# Relays_Multiplexer.net
KiCad netlist of a schematic drawn in EAGLE
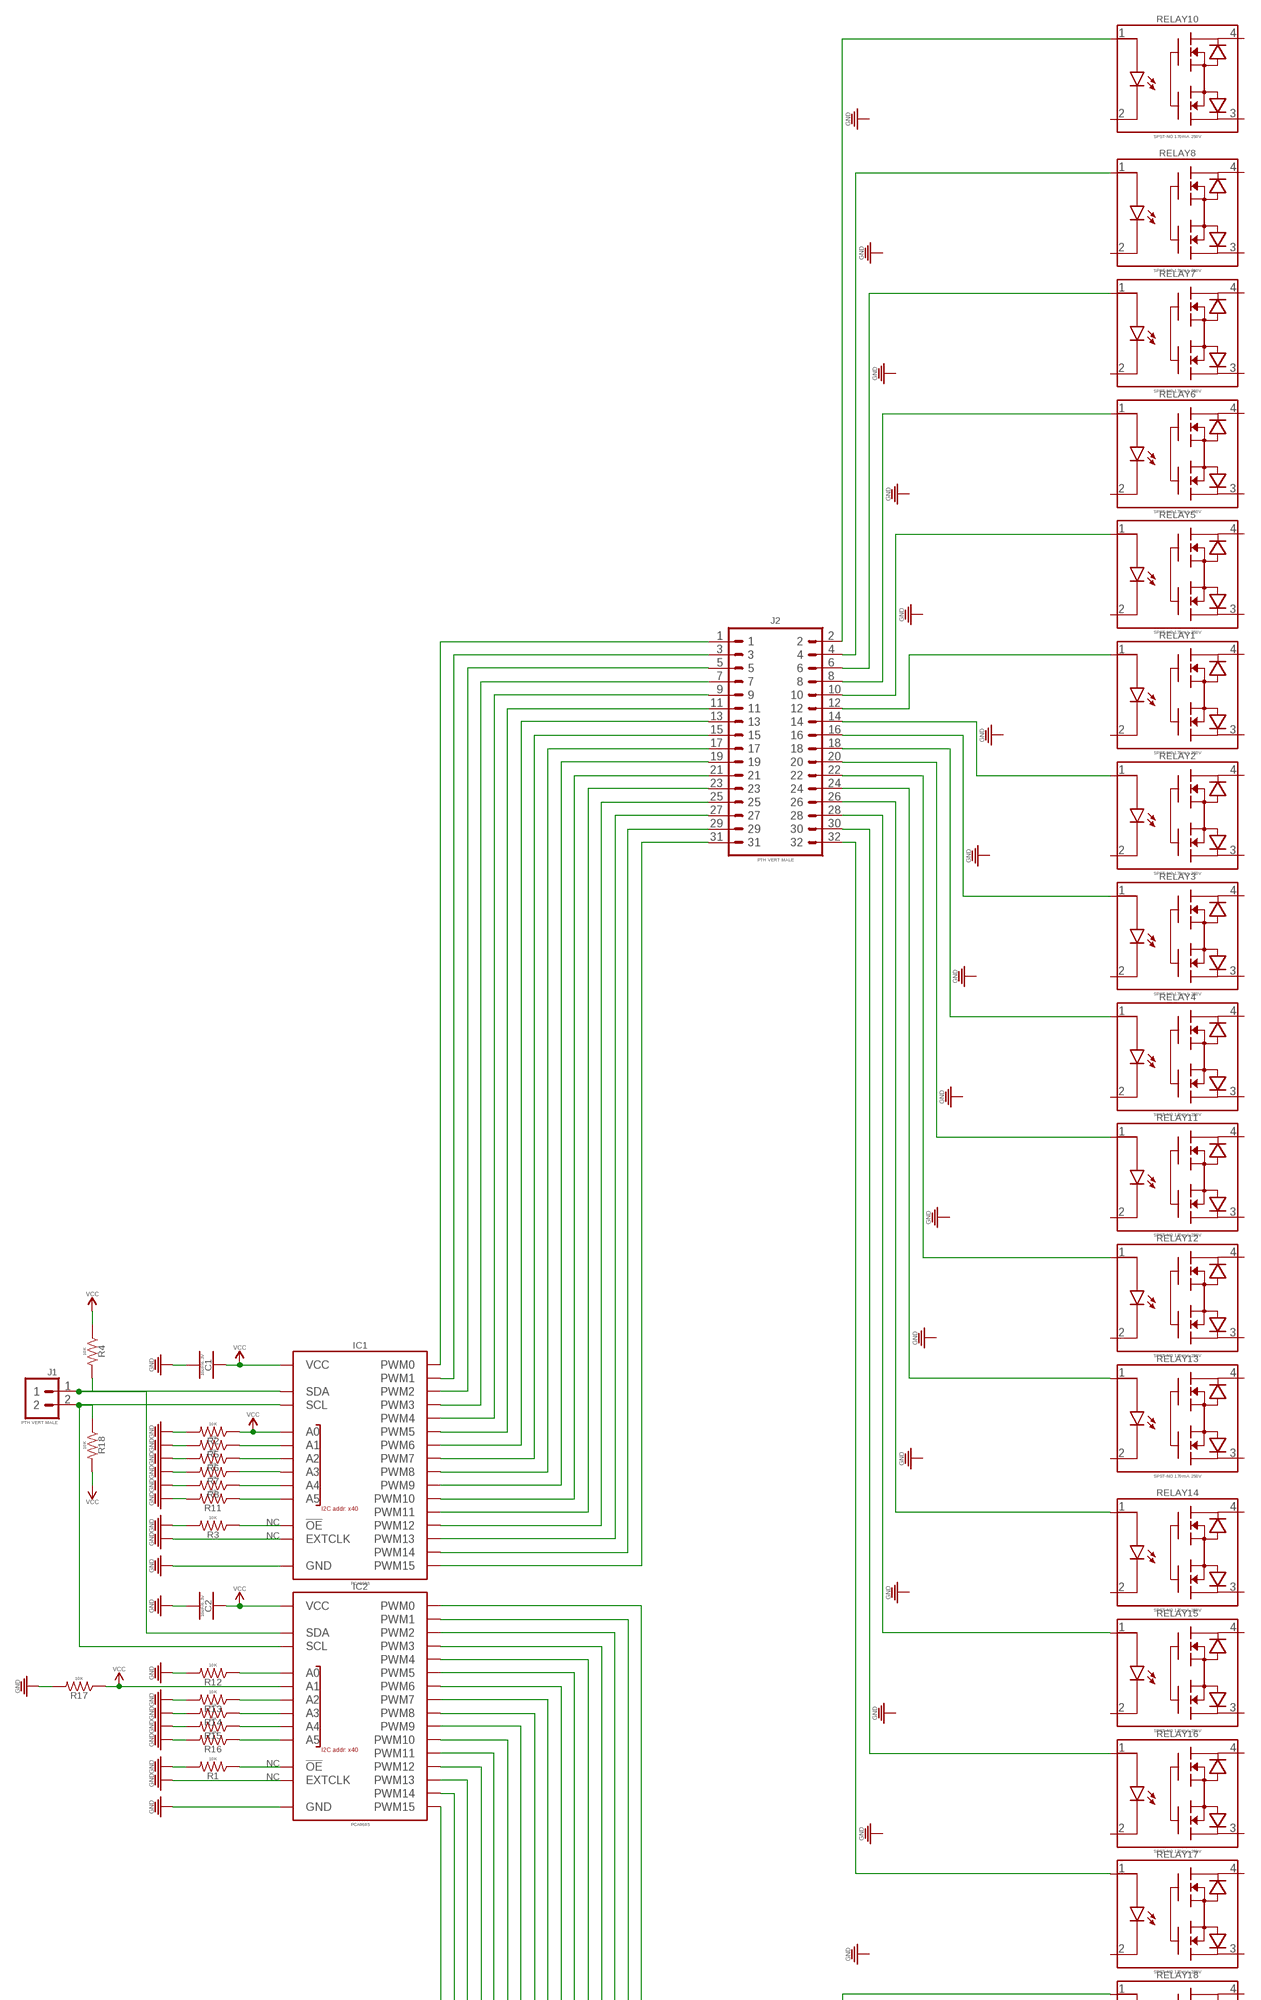
[diagram p0: schematic, sheet 1, part 1 of 2]
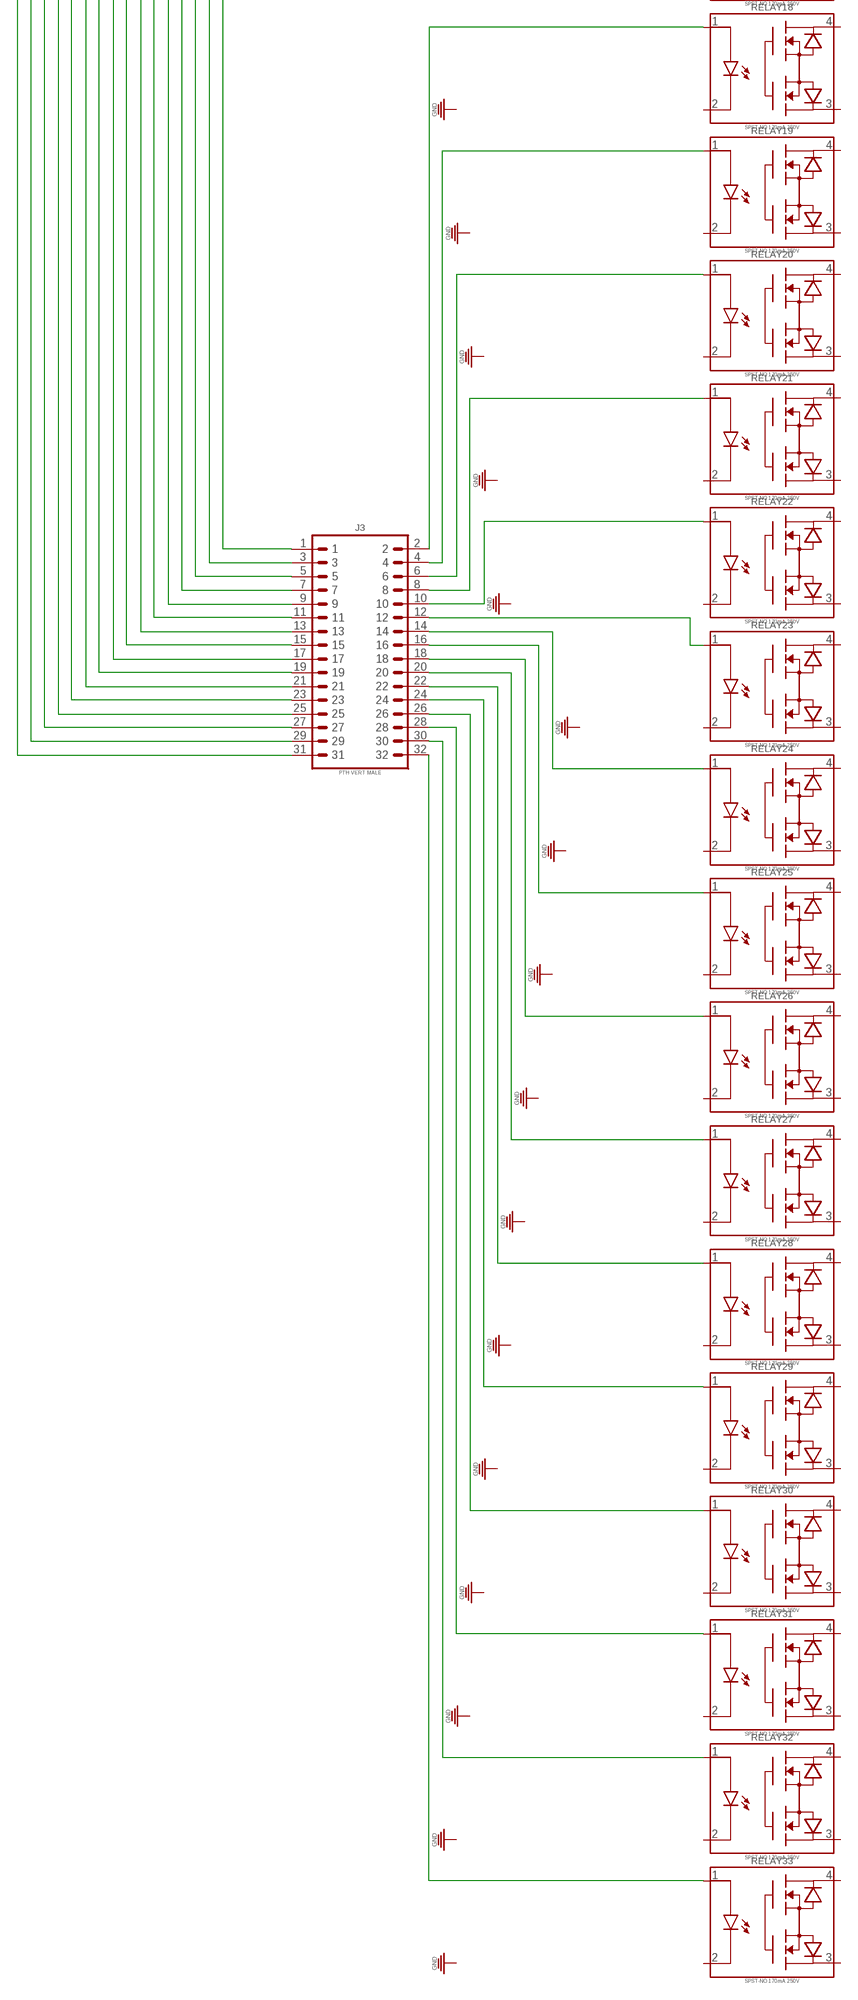
[diagram p1: schematic, sheet 1, part 2 of 2]

(export (version "E")
  (design (tool "Eeschema 10.0.6"))
  (components
    (comp (ref "C1")
      (value "10uF/6.3V")
      (footprint "eagle-import:CAPC1005X55_SMD-0402")
      (fields
        (field (name "MFR") "Murata Electronics North America")
        (field (name "MPN") "GRM155C80J106ME11D")
      )
      (libsource (lib "eagle-import") (part "10UF_CER_SMD-0402_6.3V-20%"))
    )
    (comp (ref "C2")
      (value "10uF/6.3V")
      (footprint "eagle-import:CAPC1005X55_SMD-0402")
      (fields
        (field (name "MFR") "Murata Electronics North America")
        (field (name "MPN") "GRM155C80J106ME11D")
      )
      (libsource (lib "eagle-import") (part "10UF_CER_SMD-0402_6.3V-20%"))
    )
    (comp (ref "IC1")
      (value "PCA9685")
      (footprint "eagle-import:SOP65P650X110-28")
      (fields (field (name "MFR") "NXP USA Inc.") (field (name "MPN") "PCA9685PW,118"))
      (libsource (lib "eagle-import") (part "PCA9685_16-CH_12-BIT_PWM-DRIVER_TSSOP-28_PWM-DRIVER_16CH"))
    )
    (comp (ref "IC2")
      (value "PCA9685")
      (footprint "eagle-import:SOP65P650X110-28")
      (fields (field (name "MFR") "NXP USA Inc.") (field (name "MPN") "PCA9685PW,118"))
      (libsource (lib "eagle-import") (part "PCA9685_16-CH_12-BIT_PWM-DRIVER_TSSOP-28_PWM-DRIVER_16CH"))
    )
    (comp (ref "J1")
      (value "PTH VERT MALE")
      (footprint "eagle-import:HDRV2W64P254_1X2_508X254X838B")
      (fields (field (name "MFR") "Sullins Connector Solutions") (field (name "MPN") "PEC02SAAN"))
      (libsource (lib "eagle-import") (part "1X02_PTH_VERT_MALE_2.54MM"))
    )
    (comp (ref "J2")
      (value "PTH VERT MALE")
      (footprint "eagle-import:HDRV32W64P254_2X16_4064X508X838B")
      (fields (field (name "MFR") "Sullins Connector Solutions") (field (name "MPN") "PEC16DAAN"))
      (libsource (lib "eagle-import") (part "2X16_PTH_VERT_MALE_2.54MM"))
    )
    (comp (ref "J3")
      (value "PTH VERT MALE")
      (footprint "eagle-import:HDRV32W64P254_2X16_4064X508X838B")
      (fields (field (name "MFR") "Sullins Connector Solutions") (field (name "MPN") "PEC16DAAN"))
      (libsource (lib "eagle-import") (part "2X16_PTH_VERT_MALE_2.54MM"))
    )
    (comp (ref "R1")
      (value "10K")
      (footprint "eagle-import:RESC1005X35_SMD-0402")
      (fields (field (name "MFR") "Yageo") (field (name "MPN") "RC0402JR-0710KP"))
      (libsource (lib "eagle-import") (part "10KΩ_SMD-0402_1/16W-5%"))
    )
    (comp (ref "R2")
      (value "10K")
      (footprint "eagle-import:RESC1005X35_SMD-0402")
      (fields (field (name "MFR") "Yageo") (field (name "MPN") "RC0402JR-0710KP"))
      (libsource (lib "eagle-import") (part "10KΩ_SMD-0402_1/16W-5%"))
    )
    (comp (ref "R3")
      (value "10K")
      (footprint "eagle-import:RESC1005X35_SMD-0402")
      (fields (field (name "MFR") "Yageo") (field (name "MPN") "RC0402JR-0710KP"))
      (libsource (lib "eagle-import") (part "10KΩ_SMD-0402_1/16W-5%"))
    )
    (comp (ref "R4")
      (value "10K")
      (footprint "eagle-import:RESC1005X35_SMD-0402")
      (fields (field (name "MFR") "Yageo") (field (name "MPN") "RC0402JR-0710KP"))
      (libsource (lib "eagle-import") (part "10KΩ_SMD-0402_1/16W-5%"))
    )
    (comp (ref "R5")
      (value "10K")
      (footprint "eagle-import:RESC1005X35_SMD-0402")
      (fields (field (name "MFR") "Yageo") (field (name "MPN") "RC0402JR-0710KP"))
      (libsource (lib "eagle-import") (part "10KΩ_SMD-0402_1/16W-5%"))
    )
    (comp (ref "R6")
      (value "10K")
      (footprint "eagle-import:RESC1005X35_SMD-0402")
      (fields (field (name "MFR") "Yageo") (field (name "MPN") "RC0402JR-0710KP"))
      (libsource (lib "eagle-import") (part "10KΩ_SMD-0402_1/16W-5%"))
    )
    (comp (ref "R7")
      (value "10K")
      (footprint "eagle-import:RESC1005X35_SMD-0402")
      (fields (field (name "MFR") "Yageo") (field (name "MPN") "RC0402JR-0710KP"))
      (libsource (lib "eagle-import") (part "10KΩ_SMD-0402_1/16W-5%"))
    )
    (comp (ref "R8")
      (value "10K")
      (footprint "eagle-import:RESC1005X35_SMD-0402")
      (fields (field (name "MFR") "Yageo") (field (name "MPN") "RC0402JR-0710KP"))
      (libsource (lib "eagle-import") (part "10KΩ_SMD-0402_1/16W-5%"))
    )
    (comp (ref "R11")
      (value "10K")
      (footprint "eagle-import:RESC1005X35_SMD-0402")
      (fields (field (name "MFR") "Yageo") (field (name "MPN") "RC0402JR-0710KP"))
      (libsource (lib "eagle-import") (part "10KΩ_SMD-0402_1/16W-5%"))
    )
    (comp (ref "R12")
      (value "10K")
      (footprint "eagle-import:RESC1005X35_SMD-0402")
      (fields (field (name "MFR") "Yageo") (field (name "MPN") "RC0402JR-0710KP"))
      (libsource (lib "eagle-import") (part "10KΩ_SMD-0402_1/16W-5%"))
    )
    (comp (ref "R13")
      (value "10K")
      (footprint "eagle-import:RESC1005X35_SMD-0402")
      (fields (field (name "MFR") "Yageo") (field (name "MPN") "RC0402JR-0710KP"))
      (libsource (lib "eagle-import") (part "10KΩ_SMD-0402_1/16W-5%"))
    )
    (comp (ref "R14")
      (value "10K")
      (footprint "eagle-import:RESC1005X35_SMD-0402")
      (fields (field (name "MFR") "Yageo") (field (name "MPN") "RC0402JR-0710KP"))
      (libsource (lib "eagle-import") (part "10KΩ_SMD-0402_1/16W-5%"))
    )
    (comp (ref "R15")
      (value "10K")
      (footprint "eagle-import:RESC1005X35_SMD-0402")
      (fields (field (name "MFR") "Yageo") (field (name "MPN") "RC0402JR-0710KP"))
      (libsource (lib "eagle-import") (part "10KΩ_SMD-0402_1/16W-5%"))
    )
    (comp (ref "R16")
      (value "10K")
      (footprint "eagle-import:RESC1005X35_SMD-0402")
      (fields (field (name "MFR") "Yageo") (field (name "MPN") "RC0402JR-0710KP"))
      (libsource (lib "eagle-import") (part "10KΩ_SMD-0402_1/16W-5%"))
    )
    (comp (ref "R17")
      (value "10K")
      (footprint "eagle-import:RESC1005X35_SMD-0402")
      (fields (field (name "MFR") "Yageo") (field (name "MPN") "RC0402JR-0710KP"))
      (libsource (lib "eagle-import") (part "10KΩ_SMD-0402_1/16W-5%"))
    )
    (comp (ref "R18")
      (value "10K")
      (footprint "eagle-import:RESC1005X35_SMD-0402")
      (fields (field (name "MFR") "Yageo") (field (name "MPN") "RC0402JR-0710KP"))
      (libsource (lib "eagle-import") (part "10KΩ_SMD-0402_1/16W-5%"))
    )
    (comp (ref "RELAY1")
      (value "SPST-NO 170mA 250V")
      (footprint "eagle-import:SOP254P609X203-4")
      (fields (field (name "MFR") "IXYS Integrated Circuits Division") (field (name "MPN") "CPC1010N"))
      (libsource (lib "eagle-import") (part "RELAY_SOLID-STATE_SSR_170MA_250V_SPST-NO"))
    )
    (comp (ref "RELAY2")
      (value "SPST-NO 170mA 250V")
      (footprint "eagle-import:SOP254P609X203-4")
      (fields (field (name "MFR") "IXYS Integrated Circuits Division") (field (name "MPN") "CPC1010N"))
      (libsource (lib "eagle-import") (part "RELAY_SOLID-STATE_SSR_170MA_250V_SPST-NO"))
    )
    (comp (ref "RELAY3")
      (value "SPST-NO 170mA 250V")
      (footprint "eagle-import:SOP254P609X203-4")
      (fields (field (name "MFR") "IXYS Integrated Circuits Division") (field (name "MPN") "CPC1010N"))
      (libsource (lib "eagle-import") (part "RELAY_SOLID-STATE_SSR_170MA_250V_SPST-NO"))
    )
    (comp (ref "RELAY4")
      (value "SPST-NO 170mA 250V")
      (footprint "eagle-import:SOP254P609X203-4")
      (fields (field (name "MFR") "IXYS Integrated Circuits Division") (field (name "MPN") "CPC1010N"))
      (libsource (lib "eagle-import") (part "RELAY_SOLID-STATE_SSR_170MA_250V_SPST-NO"))
    )
    (comp (ref "RELAY5")
      (value "SPST-NO 170mA 250V")
      (footprint "eagle-import:SOP254P609X203-4")
      (fields (field (name "MFR") "IXYS Integrated Circuits Division") (field (name "MPN") "CPC1010N"))
      (libsource (lib "eagle-import") (part "RELAY_SOLID-STATE_SSR_170MA_250V_SPST-NO"))
    )
    (comp (ref "RELAY6")
      (value "SPST-NO 170mA 250V")
      (footprint "eagle-import:SOP254P609X203-4")
      (fields (field (name "MFR") "IXYS Integrated Circuits Division") (field (name "MPN") "CPC1010N"))
      (libsource (lib "eagle-import") (part "RELAY_SOLID-STATE_SSR_170MA_250V_SPST-NO"))
    )
    (comp (ref "RELAY7")
      (value "SPST-NO 170mA 250V")
      (footprint "eagle-import:SOP254P609X203-4")
      (fields (field (name "MFR") "IXYS Integrated Circuits Division") (field (name "MPN") "CPC1010N"))
      (libsource (lib "eagle-import") (part "RELAY_SOLID-STATE_SSR_170MA_250V_SPST-NO"))
    )
    (comp (ref "RELAY8")
      (value "SPST-NO 170mA 250V")
      (footprint "eagle-import:SOP254P609X203-4")
      (fields (field (name "MFR") "IXYS Integrated Circuits Division") (field (name "MPN") "CPC1010N"))
      (libsource (lib "eagle-import") (part "RELAY_SOLID-STATE_SSR_170MA_250V_SPST-NO"))
    )
    (comp (ref "RELAY10")
      (value "SPST-NO 170mA 250V")
      (footprint "eagle-import:SOP254P609X203-4")
      (fields (field (name "MFR") "IXYS Integrated Circuits Division") (field (name "MPN") "CPC1010N"))
      (libsource (lib "eagle-import") (part "RELAY_SOLID-STATE_SSR_170MA_250V_SPST-NO"))
    )
    (comp (ref "RELAY11")
      (value "SPST-NO 170mA 250V")
      (footprint "eagle-import:SOP254P609X203-4")
      (fields (field (name "MFR") "IXYS Integrated Circuits Division") (field (name "MPN") "CPC1010N"))
      (libsource (lib "eagle-import") (part "RELAY_SOLID-STATE_SSR_170MA_250V_SPST-NO"))
    )
    (comp (ref "RELAY12")
      (value "SPST-NO 170mA 250V")
      (footprint "eagle-import:SOP254P609X203-4")
      (fields (field (name "MFR") "IXYS Integrated Circuits Division") (field (name "MPN") "CPC1010N"))
      (libsource (lib "eagle-import") (part "RELAY_SOLID-STATE_SSR_170MA_250V_SPST-NO"))
    )
    (comp (ref "RELAY13")
      (value "SPST-NO 170mA 250V")
      (footprint "eagle-import:SOP254P609X203-4")
      (fields (field (name "MFR") "IXYS Integrated Circuits Division") (field (name "MPN") "CPC1010N"))
      (libsource (lib "eagle-import") (part "RELAY_SOLID-STATE_SSR_170MA_250V_SPST-NO"))
    )
    (comp (ref "RELAY14")
      (value "SPST-NO 170mA 250V")
      (footprint "eagle-import:SOP254P609X203-4")
      (fields (field (name "MFR") "IXYS Integrated Circuits Division") (field (name "MPN") "CPC1010N"))
      (libsource (lib "eagle-import") (part "RELAY_SOLID-STATE_SSR_170MA_250V_SPST-NO"))
    )
    (comp (ref "RELAY15")
      (value "SPST-NO 170mA 250V")
      (footprint "eagle-import:SOP254P609X203-4")
      (fields (field (name "MFR") "IXYS Integrated Circuits Division") (field (name "MPN") "CPC1010N"))
      (libsource (lib "eagle-import") (part "RELAY_SOLID-STATE_SSR_170MA_250V_SPST-NO"))
    )
    (comp (ref "RELAY16")
      (value "SPST-NO 170mA 250V")
      (footprint "eagle-import:SOP254P609X203-4")
      (fields (field (name "MFR") "IXYS Integrated Circuits Division") (field (name "MPN") "CPC1010N"))
      (libsource (lib "eagle-import") (part "RELAY_SOLID-STATE_SSR_170MA_250V_SPST-NO"))
    )
    (comp (ref "RELAY17")
      (value "SPST-NO 170mA 250V")
      (footprint "eagle-import:SOP254P609X203-4")
      (fields (field (name "MFR") "IXYS Integrated Circuits Division") (field (name "MPN") "CPC1010N"))
      (libsource (lib "eagle-import") (part "RELAY_SOLID-STATE_SSR_170MA_250V_SPST-NO"))
    )
    (comp (ref "RELAY18")
      (value "SPST-NO 170mA 250V")
      (footprint "eagle-import:SOP254P609X203-4")
      (fields (field (name "MFR") "IXYS Integrated Circuits Division") (field (name "MPN") "CPC1010N"))
      (libsource (lib "eagle-import") (part "RELAY_SOLID-STATE_SSR_170MA_250V_SPST-NO"))
    )
    (comp (ref "RELAY19")
      (value "SPST-NO 170mA 250V")
      (footprint "eagle-import:SOP254P609X203-4")
      (fields (field (name "MFR") "IXYS Integrated Circuits Division") (field (name "MPN") "CPC1010N"))
      (libsource (lib "eagle-import") (part "RELAY_SOLID-STATE_SSR_170MA_250V_SPST-NO"))
    )
    (comp (ref "RELAY20")
      (value "SPST-NO 170mA 250V")
      (footprint "eagle-import:SOP254P609X203-4")
      (fields (field (name "MFR") "IXYS Integrated Circuits Division") (field (name "MPN") "CPC1010N"))
      (libsource (lib "eagle-import") (part "RELAY_SOLID-STATE_SSR_170MA_250V_SPST-NO"))
    )
    (comp (ref "RELAY21")
      (value "SPST-NO 170mA 250V")
      (footprint "eagle-import:SOP254P609X203-4")
      (fields (field (name "MFR") "IXYS Integrated Circuits Division") (field (name "MPN") "CPC1010N"))
      (libsource (lib "eagle-import") (part "RELAY_SOLID-STATE_SSR_170MA_250V_SPST-NO"))
    )
    (comp (ref "RELAY22")
      (value "SPST-NO 170mA 250V")
      (footprint "eagle-import:SOP254P609X203-4")
      (fields (field (name "MFR") "IXYS Integrated Circuits Division") (field (name "MPN") "CPC1010N"))
      (libsource (lib "eagle-import") (part "RELAY_SOLID-STATE_SSR_170MA_250V_SPST-NO"))
    )
    (comp (ref "RELAY23")
      (value "SPST-NO 170mA 250V")
      (footprint "eagle-import:SOP254P609X203-4")
      (fields (field (name "MFR") "IXYS Integrated Circuits Division") (field (name "MPN") "CPC1010N"))
      (libsource (lib "eagle-import") (part "RELAY_SOLID-STATE_SSR_170MA_250V_SPST-NO"))
    )
    (comp (ref "RELAY24")
      (value "SPST-NO 170mA 250V")
      (footprint "eagle-import:SOP254P609X203-4")
      (fields (field (name "MFR") "IXYS Integrated Circuits Division") (field (name "MPN") "CPC1010N"))
      (libsource (lib "eagle-import") (part "RELAY_SOLID-STATE_SSR_170MA_250V_SPST-NO"))
    )
    (comp (ref "RELAY25")
      (value "SPST-NO 170mA 250V")
      (footprint "eagle-import:SOP254P609X203-4")
      (fields (field (name "MFR") "IXYS Integrated Circuits Division") (field (name "MPN") "CPC1010N"))
      (libsource (lib "eagle-import") (part "RELAY_SOLID-STATE_SSR_170MA_250V_SPST-NO"))
    )
    (comp (ref "RELAY26")
      (value "SPST-NO 170mA 250V")
      (footprint "eagle-import:SOP254P609X203-4")
      (fields (field (name "MFR") "IXYS Integrated Circuits Division") (field (name "MPN") "CPC1010N"))
      (libsource (lib "eagle-import") (part "RELAY_SOLID-STATE_SSR_170MA_250V_SPST-NO"))
    )
    (comp (ref "RELAY27")
      (value "SPST-NO 170mA 250V")
      (footprint "eagle-import:SOP254P609X203-4")
      (fields (field (name "MFR") "IXYS Integrated Circuits Division") (field (name "MPN") "CPC1010N"))
      (libsource (lib "eagle-import") (part "RELAY_SOLID-STATE_SSR_170MA_250V_SPST-NO"))
    )
    (comp (ref "RELAY28")
      (value "SPST-NO 170mA 250V")
      (footprint "eagle-import:SOP254P609X203-4")
      (fields (field (name "MFR") "IXYS Integrated Circuits Division") (field (name "MPN") "CPC1010N"))
      (libsource (lib "eagle-import") (part "RELAY_SOLID-STATE_SSR_170MA_250V_SPST-NO"))
    )
    (comp (ref "RELAY29")
      (value "SPST-NO 170mA 250V")
      (footprint "eagle-import:SOP254P609X203-4")
      (fields (field (name "MFR") "IXYS Integrated Circuits Division") (field (name "MPN") "CPC1010N"))
      (libsource (lib "eagle-import") (part "RELAY_SOLID-STATE_SSR_170MA_250V_SPST-NO"))
    )
    (comp (ref "RELAY30")
      (value "SPST-NO 170mA 250V")
      (footprint "eagle-import:SOP254P609X203-4")
      (fields (field (name "MFR") "IXYS Integrated Circuits Division") (field (name "MPN") "CPC1010N"))
      (libsource (lib "eagle-import") (part "RELAY_SOLID-STATE_SSR_170MA_250V_SPST-NO"))
    )
    (comp (ref "RELAY31")
      (value "SPST-NO 170mA 250V")
      (footprint "eagle-import:SOP254P609X203-4")
      (fields (field (name "MFR") "IXYS Integrated Circuits Division") (field (name "MPN") "CPC1010N"))
      (libsource (lib "eagle-import") (part "RELAY_SOLID-STATE_SSR_170MA_250V_SPST-NO"))
    )
    (comp (ref "RELAY32")
      (value "SPST-NO 170mA 250V")
      (footprint "eagle-import:SOP254P609X203-4")
      (fields (field (name "MFR") "IXYS Integrated Circuits Division") (field (name "MPN") "CPC1010N"))
      (libsource (lib "eagle-import") (part "RELAY_SOLID-STATE_SSR_170MA_250V_SPST-NO"))
    )
    (comp (ref "RELAY33")
      (value "SPST-NO 170mA 250V")
      (footprint "eagle-import:SOP254P609X203-4")
      (fields (field (name "MFR") "IXYS Integrated Circuits Division") (field (name "MPN") "CPC1010N"))
      (libsource (lib "eagle-import") (part "RELAY_SOLID-STATE_SSR_170MA_250V_SPST-NO"))
    )
  )
  (nets
    (net (code "1") (name "GND") (class "Default")
      (node (ref "C1") (pin "2") (pinfunction "2_2") (pintype "passive"))
      (node (ref "C2") (pin "2") (pinfunction "2_2") (pintype "passive"))
      (node (ref "IC1") (pin "14") (pinfunction "GND_14") (pintype "power_in"))
      (node (ref "IC1") (pin "25") (pinfunction "EXTCLK_25") (pintype "power_in"))
      (node (ref "IC2") (pin "14") (pinfunction "GND_14") (pintype "power_in"))
      (node (ref "IC2") (pin "25") (pinfunction "EXTCLK_25") (pintype "power_in"))
      (node (ref "R1") (pin "2") (pinfunction "2_2") (pintype "passive"))
      (node (ref "R11") (pin "2") (pinfunction "2_2") (pintype "passive"))
      (node (ref "R12") (pin "2") (pinfunction "2_2") (pintype "passive"))
      (node (ref "R13") (pin "2") (pinfunction "2_2") (pintype "passive"))
      (node (ref "R14") (pin "2") (pinfunction "2_2") (pintype "passive"))
      (node (ref "R15") (pin "2") (pinfunction "2_2") (pintype "passive"))
      (node (ref "R16") (pin "2") (pinfunction "2_2") (pintype "passive"))
      (node (ref "R17") (pin "2") (pinfunction "2_2") (pintype "passive"))
      (node (ref "R2") (pin "2") (pinfunction "2_2") (pintype "passive"))
      (node (ref "R3") (pin "2") (pinfunction "2_2") (pintype "passive"))
      (node (ref "R5") (pin "2") (pinfunction "2_2") (pintype "passive"))
      (node (ref "R6") (pin "2") (pinfunction "2_2") (pintype "passive"))
      (node (ref "R7") (pin "2") (pinfunction "2_2") (pintype "passive"))
      (node (ref "R8") (pin "2") (pinfunction "2_2") (pintype "passive"))
    )
    (net (code "2") (name "Net-(IC1-A1)") (class "Default")
      (node (ref "IC1") (pin "2") (pinfunction "A1_2") (pintype "power_in"))
      (node (ref "R5") (pin "1") (pinfunction "1_1") (pintype "passive"))
    )
    (net (code "3") (name "Net-(IC1-A2)") (class "Default")
      (node (ref "IC1") (pin "3") (pinfunction "A2_3") (pintype "power_in"))
      (node (ref "R6") (pin "1") (pinfunction "1_1") (pintype "passive"))
    )
    (net (code "4") (name "Net-(IC1-A3)") (class "Default")
      (node (ref "IC1") (pin "4") (pinfunction "A3_4") (pintype "power_in"))
      (node (ref "R7") (pin "1") (pinfunction "1_1") (pintype "passive"))
    )
    (net (code "5") (name "Net-(IC1-A4)") (class "Default")
      (node (ref "IC1") (pin "5") (pinfunction "A4_5") (pintype "power_in"))
      (node (ref "R8") (pin "1") (pinfunction "1_1") (pintype "passive"))
    )
    (net (code "6") (name "Net-(IC1-A5)") (class "Default")
      (node (ref "IC1") (pin "24") (pinfunction "A5_24") (pintype "power_in"))
      (node (ref "R11") (pin "1") (pinfunction "1_1") (pintype "passive"))
    )
    (net (code "7") (name "Net-(IC1-PWM0)") (class "Default")
      (node (ref "IC1") (pin "6") (pinfunction "PWM0_6") (pintype "output"))
      (node (ref "J2") (pin "1") (pinfunction "1_1") (pintype "passive"))
    )
    (net (code "8") (name "Net-(IC1-PWM1)") (class "Default")
      (node (ref "IC1") (pin "7") (pinfunction "PWM1_7") (pintype "output"))
      (node (ref "J2") (pin "3") (pinfunction "3_3") (pintype "passive"))
    )
    (net (code "9") (name "Net-(IC1-PWM2)") (class "Default")
      (node (ref "IC1") (pin "8") (pinfunction "PWM2_8") (pintype "output"))
      (node (ref "J2") (pin "5") (pinfunction "5_5") (pintype "passive"))
    )
    (net (code "10") (name "Net-(IC1-PWM3)") (class "Default")
      (node (ref "IC1") (pin "9") (pinfunction "PWM3_9") (pintype "output"))
      (node (ref "J2") (pin "7") (pinfunction "7_7") (pintype "passive"))
    )
    (net (code "11") (name "Net-(IC1-PWM4)") (class "Default")
      (node (ref "IC1") (pin "10") (pinfunction "PWM4_10") (pintype "output"))
      (node (ref "J2") (pin "9") (pinfunction "9_9") (pintype "passive"))
    )
    (net (code "12") (name "Net-(IC1-PWM5)") (class "Default")
      (node (ref "IC1") (pin "11") (pinfunction "PWM5_11") (pintype "output"))
      (node (ref "J2") (pin "11") (pinfunction "11_11") (pintype "passive"))
    )
    (net (code "13") (name "Net-(IC1-PWM6)") (class "Default")
      (node (ref "IC1") (pin "12") (pinfunction "PWM6_12") (pintype "output"))
      (node (ref "J2") (pin "13") (pinfunction "13_13") (pintype "passive"))
    )
    (net (code "14") (name "Net-(IC1-PWM7)") (class "Default")
      (node (ref "IC1") (pin "13") (pinfunction "PWM7_13") (pintype "output"))
      (node (ref "J2") (pin "15") (pinfunction "15_15") (pintype "passive"))
    )
    (net (code "15") (name "Net-(IC1-PWM8)") (class "Default")
      (node (ref "IC1") (pin "15") (pinfunction "PWM8_15") (pintype "output"))
      (node (ref "J2") (pin "17") (pinfunction "17_17") (pintype "passive"))
    )
    (net (code "16") (name "Net-(IC1-PWM9)") (class "Default")
      (node (ref "IC1") (pin "16") (pinfunction "PWM9_16") (pintype "output"))
      (node (ref "J2") (pin "19") (pinfunction "19_19") (pintype "passive"))
    )
    (net (code "17") (name "Net-(IC1-PWM10)") (class "Default")
      (node (ref "IC1") (pin "17") (pinfunction "PWM10_17") (pintype "output"))
      (node (ref "J2") (pin "21") (pinfunction "21_21") (pintype "passive"))
    )
    (net (code "18") (name "Net-(IC1-PWM11)") (class "Default")
      (node (ref "IC1") (pin "18") (pinfunction "PWM11_18") (pintype "output"))
      (node (ref "J2") (pin "23") (pinfunction "23_23") (pintype "passive"))
    )
    (net (code "19") (name "Net-(IC1-PWM12)") (class "Default")
      (node (ref "IC1") (pin "19") (pinfunction "PWM12_19") (pintype "output"))
      (node (ref "J2") (pin "25") (pinfunction "25_25") (pintype "passive"))
    )
    (net (code "20") (name "Net-(IC1-PWM13)") (class "Default")
      (node (ref "IC1") (pin "20") (pinfunction "PWM13_20") (pintype "output"))
      (node (ref "J2") (pin "27") (pinfunction "27_27") (pintype "passive"))
    )
    (net (code "21") (name "Net-(IC1-PWM14)") (class "Default")
      (node (ref "IC1") (pin "21") (pinfunction "PWM14_21") (pintype "output"))
      (node (ref "J2") (pin "29") (pinfunction "29_29") (pintype "passive"))
    )
    (net (code "22") (name "Net-(IC1-PWM15)") (class "Default")
      (node (ref "IC1") (pin "22") (pinfunction "PWM15_22") (pintype "output"))
      (node (ref "J2") (pin "31") (pinfunction "31_31") (pintype "passive"))
    )
    (net (code "23") (name "Net-(IC1-SCL)") (class "Default")
      (node (ref "IC1") (pin "26") (pinfunction "SCL_26") (pintype "bidirectional"))
      (node (ref "IC2") (pin "26") (pinfunction "SCL_26") (pintype "bidirectional"))
      (node (ref "J1") (pin "2") (pinfunction "2_2") (pintype "passive"))
      (node (ref "R18") (pin "1") (pinfunction "1_1") (pintype "passive"))
    )
    (net (code "24") (name "Net-(IC1-SDA)") (class "Default")
      (node (ref "IC1") (pin "27") (pinfunction "SDA_27") (pintype "bidirectional"))
      (node (ref "IC2") (pin "27") (pinfunction "SDA_27") (pintype "bidirectional"))
      (node (ref "J1") (pin "1") (pinfunction "1_1") (pintype "passive"))
      (node (ref "R4") (pin "2") (pinfunction "2_2") (pintype "passive"))
    )
    (net (code "25") (name "Net-(IC1-~{OE})") (class "Default")
      (node (ref "IC1") (pin "23") (pinfunction "~{OE}_23") (pintype "power_in"))
      (node (ref "R3") (pin "1") (pinfunction "1_1") (pintype "passive"))
    )
    (net (code "26") (name "Net-(IC2-A0)") (class "Default")
      (node (ref "IC2") (pin "1") (pinfunction "A0_1") (pintype "power_in"))
      (node (ref "R12") (pin "1") (pinfunction "1_1") (pintype "passive"))
    )
    (net (code "27") (name "Net-(IC2-A2)") (class "Default")
      (node (ref "IC2") (pin "3") (pinfunction "A2_3") (pintype "power_in"))
      (node (ref "R13") (pin "1") (pinfunction "1_1") (pintype "passive"))
    )
    (net (code "28") (name "Net-(IC2-A3)") (class "Default")
      (node (ref "IC2") (pin "4") (pinfunction "A3_4") (pintype "power_in"))
      (node (ref "R14") (pin "1") (pinfunction "1_1") (pintype "passive"))
    )
    (net (code "29") (name "Net-(IC2-A4)") (class "Default")
      (node (ref "IC2") (pin "5") (pinfunction "A4_5") (pintype "power_in"))
      (node (ref "R15") (pin "1") (pinfunction "1_1") (pintype "passive"))
    )
    (net (code "30") (name "Net-(IC2-A5)") (class "Default")
      (node (ref "IC2") (pin "24") (pinfunction "A5_24") (pintype "power_in"))
      (node (ref "R16") (pin "1") (pinfunction "1_1") (pintype "passive"))
    )
    (net (code "31") (name "Net-(IC2-PWM0)") (class "Default")
      (node (ref "IC2") (pin "6") (pinfunction "PWM0_6") (pintype "output"))
      (node (ref "J3") (pin "1") (pinfunction "1_1") (pintype "passive"))
    )
    (net (code "32") (name "Net-(IC2-PWM1)") (class "Default")
      (node (ref "IC2") (pin "7") (pinfunction "PWM1_7") (pintype "output"))
      (node (ref "J3") (pin "3") (pinfunction "3_3") (pintype "passive"))
    )
    (net (code "33") (name "Net-(IC2-PWM2)") (class "Default")
      (node (ref "IC2") (pin "8") (pinfunction "PWM2_8") (pintype "output"))
      (node (ref "J3") (pin "5") (pinfunction "5_5") (pintype "passive"))
    )
    (net (code "34") (name "Net-(IC2-PWM3)") (class "Default")
      (node (ref "IC2") (pin "9") (pinfunction "PWM3_9") (pintype "output"))
      (node (ref "J3") (pin "7") (pinfunction "7_7") (pintype "passive"))
    )
    (net (code "35") (name "Net-(IC2-PWM4)") (class "Default")
      (node (ref "IC2") (pin "10") (pinfunction "PWM4_10") (pintype "output"))
      (node (ref "J3") (pin "9") (pinfunction "9_9") (pintype "passive"))
    )
    (net (code "36") (name "Net-(IC2-PWM5)") (class "Default")
      (node (ref "IC2") (pin "11") (pinfunction "PWM5_11") (pintype "output"))
      (node (ref "J3") (pin "11") (pinfunction "11_11") (pintype "passive"))
    )
    (net (code "37") (name "Net-(IC2-PWM6)") (class "Default")
      (node (ref "IC2") (pin "12") (pinfunction "PWM6_12") (pintype "output"))
      (node (ref "J3") (pin "13") (pinfunction "13_13") (pintype "passive"))
    )
    (net (code "38") (name "Net-(IC2-PWM7)") (class "Default")
      (node (ref "IC2") (pin "13") (pinfunction "PWM7_13") (pintype "output"))
      (node (ref "J3") (pin "15") (pinfunction "15_15") (pintype "passive"))
    )
    (net (code "39") (name "Net-(IC2-PWM8)") (class "Default")
      (node (ref "IC2") (pin "15") (pinfunction "PWM8_15") (pintype "output"))
      (node (ref "J3") (pin "17") (pinfunction "17_17") (pintype "passive"))
    )
    (net (code "40") (name "Net-(IC2-PWM9)") (class "Default")
      (node (ref "IC2") (pin "16") (pinfunction "PWM9_16") (pintype "output"))
      (node (ref "J3") (pin "19") (pinfunction "19_19") (pintype "passive"))
    )
    (net (code "41") (name "Net-(IC2-PWM10)") (class "Default")
      (node (ref "IC2") (pin "17") (pinfunction "PWM10_17") (pintype "output"))
      (node (ref "J3") (pin "21") (pinfunction "21_21") (pintype "passive"))
    )
    (net (code "42") (name "Net-(IC2-PWM11)") (class "Default")
      (node (ref "IC2") (pin "18") (pinfunction "PWM11_18") (pintype "output"))
      (node (ref "J3") (pin "23") (pinfunction "23_23") (pintype "passive"))
    )
    (net (code "43") (name "Net-(IC2-PWM12)") (class "Default")
      (node (ref "IC2") (pin "19") (pinfunction "PWM12_19") (pintype "output"))
      (node (ref "J3") (pin "25") (pinfunction "25_25") (pintype "passive"))
    )
    (net (code "44") (name "Net-(IC2-PWM13)") (class "Default")
      (node (ref "IC2") (pin "20") (pinfunction "PWM13_20") (pintype "output"))
      (node (ref "J3") (pin "27") (pinfunction "27_27") (pintype "passive"))
    )
    (net (code "45") (name "Net-(IC2-PWM14)") (class "Default")
      (node (ref "IC2") (pin "21") (pinfunction "PWM14_21") (pintype "output"))
      (node (ref "J3") (pin "29") (pinfunction "29_29") (pintype "passive"))
    )
    (net (code "46") (name "Net-(IC2-PWM15)") (class "Default")
      (node (ref "IC2") (pin "22") (pinfunction "PWM15_22") (pintype "output"))
      (node (ref "J3") (pin "31") (pinfunction "31_31") (pintype "passive"))
    )
    (net (code "47") (name "Net-(IC2-~{OE})") (class "Default")
      (node (ref "IC2") (pin "23") (pinfunction "~{OE}_23") (pintype "power_in"))
      (node (ref "R1") (pin "1") (pinfunction "1_1") (pintype "passive"))
    )
    (net (code "48") (name "Net-(J2-Pad2)") (class "Default")
      (node (ref "J2") (pin "2") (pinfunction "2_2") (pintype "passive"))
      (node (ref "RELAY10") (pin "1") (pinfunction "1_1") (pintype "bidirectional"))
    )
    (net (code "49") (name "Net-(J2-Pad4)") (class "Default")
      (node (ref "J2") (pin "4") (pinfunction "4_4") (pintype "passive"))
      (node (ref "RELAY8") (pin "1") (pinfunction "1_1") (pintype "bidirectional"))
    )
    (net (code "50") (name "Net-(J2-Pad6)") (class "Default")
      (node (ref "J2") (pin "6") (pinfunction "6_6") (pintype "passive"))
      (node (ref "RELAY7") (pin "1") (pinfunction "1_1") (pintype "bidirectional"))
    )
    (net (code "51") (name "Net-(J2-Pad8)") (class "Default")
      (node (ref "J2") (pin "8") (pinfunction "8_8") (pintype "passive"))
      (node (ref "RELAY6") (pin "1") (pinfunction "1_1") (pintype "bidirectional"))
    )
    (net (code "52") (name "Net-(J2-Pad10)") (class "Default")
      (node (ref "J2") (pin "10") (pinfunction "10_10") (pintype "passive"))
      (node (ref "RELAY5") (pin "1") (pinfunction "1_1") (pintype "bidirectional"))
    )
    (net (code "53") (name "Net-(J2-Pad12)") (class "Default")
      (node (ref "J2") (pin "12") (pinfunction "12_12") (pintype "passive"))
      (node (ref "RELAY1") (pin "1") (pinfunction "1_1") (pintype "bidirectional"))
    )
    (net (code "54") (name "Net-(J2-Pad14)") (class "Default")
      (node (ref "J2") (pin "14") (pinfunction "14_14") (pintype "passive"))
      (node (ref "RELAY2") (pin "1") (pinfunction "1_1") (pintype "bidirectional"))
    )
    (net (code "55") (name "Net-(J2-Pad16)") (class "Default")
      (node (ref "J2") (pin "16") (pinfunction "16_16") (pintype "passive"))
      (node (ref "RELAY3") (pin "1") (pinfunction "1_1") (pintype "bidirectional"))
    )
    (net (code "56") (name "Net-(J2-Pad18)") (class "Default")
      (node (ref "J2") (pin "18") (pinfunction "18_18") (pintype "passive"))
      (node (ref "RELAY4") (pin "1") (pinfunction "1_1") (pintype "bidirectional"))
    )
    (net (code "57") (name "Net-(J2-Pad20)") (class "Default")
      (node (ref "J2") (pin "20") (pinfunction "20_20") (pintype "passive"))
      (node (ref "RELAY11") (pin "1") (pinfunction "1_1") (pintype "bidirectional"))
    )
    (net (code "58") (name "Net-(J2-Pad22)") (class "Default")
      (node (ref "J2") (pin "22") (pinfunction "22_22") (pintype "passive"))
      (node (ref "RELAY12") (pin "1") (pinfunction "1_1") (pintype "bidirectional"))
    )
    (net (code "59") (name "Net-(J2-Pad24)") (class "Default")
      (node (ref "J2") (pin "24") (pinfunction "24_24") (pintype "passive"))
      (node (ref "RELAY13") (pin "1") (pinfunction "1_1") (pintype "bidirectional"))
    )
    (net (code "60") (name "Net-(J2-Pad26)") (class "Default")
      (node (ref "J2") (pin "26") (pinfunction "26_26") (pintype "passive"))
      (node (ref "RELAY14") (pin "1") (pinfunction "1_1") (pintype "bidirectional"))
    )
    (net (code "61") (name "Net-(J2-Pad28)") (class "Default")
      (node (ref "J2") (pin "28") (pinfunction "28_28") (pintype "passive"))
      (node (ref "RELAY15") (pin "1") (pinfunction "1_1") (pintype "bidirectional"))
    )
    (net (code "62") (name "Net-(J2-Pad30)") (class "Default")
      (node (ref "J2") (pin "30") (pinfunction "30_30") (pintype "passive"))
      (node (ref "RELAY16") (pin "1") (pinfunction "1_1") (pintype "bidirectional"))
    )
    (net (code "63") (name "Net-(J2-Pad32)") (class "Default")
      (node (ref "J2") (pin "32") (pinfunction "32_32") (pintype "passive"))
      (node (ref "RELAY17") (pin "1") (pinfunction "1_1") (pintype "bidirectional"))
    )
    (net (code "64") (name "Net-(J3-Pad2)") (class "Default")
      (node (ref "J3") (pin "2") (pinfunction "2_2") (pintype "passive"))
      (node (ref "RELAY18") (pin "1") (pinfunction "1_1") (pintype "bidirectional"))
    )
    (net (code "65") (name "Net-(J3-Pad4)") (class "Default")
      (node (ref "J3") (pin "4") (pinfunction "4_4") (pintype "passive"))
      (node (ref "RELAY19") (pin "1") (pinfunction "1_1") (pintype "bidirectional"))
    )
    (net (code "66") (name "Net-(J3-Pad6)") (class "Default")
      (node (ref "J3") (pin "6") (pinfunction "6_6") (pintype "passive"))
      (node (ref "RELAY20") (pin "1") (pinfunction "1_1") (pintype "bidirectional"))
    )
    (net (code "67") (name "Net-(J3-Pad8)") (class "Default")
      (node (ref "J3") (pin "8") (pinfunction "8_8") (pintype "passive"))
      (node (ref "RELAY21") (pin "1") (pinfunction "1_1") (pintype "bidirectional"))
    )
    (net (code "68") (name "Net-(J3-Pad10)") (class "Default")
      (node (ref "J3") (pin "10") (pinfunction "10_10") (pintype "passive"))
      (node (ref "RELAY22") (pin "1") (pinfunction "1_1") (pintype "bidirectional"))
    )
    (net (code "69") (name "Net-(J3-Pad12)") (class "Default")
      (node (ref "J3") (pin "12") (pinfunction "12_12") (pintype "passive"))
      (node (ref "RELAY23") (pin "1") (pinfunction "1_1") (pintype "bidirectional"))
    )
    (net (code "70") (name "Net-(J3-Pad14)") (class "Default")
      (node (ref "J3") (pin "14") (pinfunction "14_14") (pintype "passive"))
      (node (ref "RELAY24") (pin "1") (pinfunction "1_1") (pintype "bidirectional"))
    )
    (net (code "71") (name "Net-(J3-Pad16)") (class "Default")
      (node (ref "J3") (pin "16") (pinfunction "16_16") (pintype "passive"))
      (node (ref "RELAY25") (pin "1") (pinfunction "1_1") (pintype "bidirectional"))
    )
    (net (code "72") (name "Net-(J3-Pad18)") (class "Default")
      (node (ref "J3") (pin "18") (pinfunction "18_18") (pintype "passive"))
      (node (ref "RELAY26") (pin "1") (pinfunction "1_1") (pintype "bidirectional"))
    )
    (net (code "73") (name "Net-(J3-Pad20)") (class "Default")
      (node (ref "J3") (pin "20") (pinfunction "20_20") (pintype "passive"))
      (node (ref "RELAY27") (pin "1") (pinfunction "1_1") (pintype "bidirectional"))
    )
    (net (code "74") (name "Net-(J3-Pad22)") (class "Default")
      (node (ref "J3") (pin "22") (pinfunction "22_22") (pintype "passive"))
      (node (ref "RELAY28") (pin "1") (pinfunction "1_1") (pintype "bidirectional"))
    )
    (net (code "75") (name "Net-(J3-Pad24)") (class "Default")
      (node (ref "J3") (pin "24") (pinfunction "24_24") (pintype "passive"))
      (node (ref "RELAY29") (pin "1") (pinfunction "1_1") (pintype "bidirectional"))
    )
    (net (code "76") (name "Net-(J3-Pad26)") (class "Default")
      (node (ref "J3") (pin "26") (pinfunction "26_26") (pintype "passive"))
      (node (ref "RELAY30") (pin "1") (pinfunction "1_1") (pintype "bidirectional"))
    )
    (net (code "77") (name "Net-(J3-Pad28)") (class "Default")
      (node (ref "J3") (pin "28") (pinfunction "28_28") (pintype "passive"))
      (node (ref "RELAY31") (pin "1") (pinfunction "1_1") (pintype "bidirectional"))
    )
    (net (code "78") (name "Net-(J3-Pad30)") (class "Default")
      (node (ref "J3") (pin "30") (pinfunction "30_30") (pintype "passive"))
      (node (ref "RELAY32") (pin "1") (pinfunction "1_1") (pintype "bidirectional"))
    )
    (net (code "79") (name "Net-(J3-Pad32)") (class "Default")
      (node (ref "J3") (pin "32") (pinfunction "32_32") (pintype "passive"))
      (node (ref "RELAY33") (pin "1") (pinfunction "1_1") (pintype "bidirectional"))
    )
    (net (code "80") (name "VCC") (class "Default")
      (node (ref "C1") (pin "1") (pinfunction "1_1") (pintype "passive"))
      (node (ref "C2") (pin "1") (pinfunction "1_1") (pintype "passive"))
      (node (ref "IC1") (pin "1") (pinfunction "A0_1") (pintype "power_in"))
      (node (ref "IC1") (pin "28") (pinfunction "VCC_28") (pintype "power_in"))
      (node (ref "IC2") (pin "2") (pinfunction "A1_2") (pintype "power_in"))
      (node (ref "IC2") (pin "28") (pinfunction "VCC_28") (pintype "power_in"))
      (node (ref "R17") (pin "1") (pinfunction "1_1") (pintype "passive"))
      (node (ref "R18") (pin "2") (pinfunction "2_2") (pintype "passive"))
      (node (ref "R2") (pin "1") (pinfunction "1_1") (pintype "passive"))
      (node (ref "R4") (pin "1") (pinfunction "1_1") (pintype "passive"))
    )
    (net (code "81") (name "unconnected-(RELAY1-Pad2)") (class "Default")
      (node (ref "RELAY1") (pin "2") (pinfunction "2_2") (pintype "bidirectional"))
    )
    (net (code "82") (name "unconnected-(RELAY1-Pad3)") (class "Default")
      (node (ref "RELAY1") (pin "3") (pinfunction "3_3") (pintype "bidirectional"))
    )
    (net (code "83") (name "unconnected-(RELAY1-Pad4)") (class "Default")
      (node (ref "RELAY1") (pin "4") (pinfunction "4_4") (pintype "bidirectional"))
    )
    (net (code "84") (name "unconnected-(RELAY2-Pad2)") (class "Default")
      (node (ref "RELAY2") (pin "2") (pinfunction "2_2") (pintype "bidirectional"))
    )
    (net (code "85") (name "unconnected-(RELAY2-Pad3)") (class "Default")
      (node (ref "RELAY2") (pin "3") (pinfunction "3_3") (pintype "bidirectional"))
    )
    (net (code "86") (name "unconnected-(RELAY2-Pad4)") (class "Default")
      (node (ref "RELAY2") (pin "4") (pinfunction "4_4") (pintype "bidirectional"))
    )
    (net (code "87") (name "unconnected-(RELAY3-Pad2)") (class "Default")
      (node (ref "RELAY3") (pin "2") (pinfunction "2_2") (pintype "bidirectional"))
    )
    (net (code "88") (name "unconnected-(RELAY3-Pad3)") (class "Default")
      (node (ref "RELAY3") (pin "3") (pinfunction "3_3") (pintype "bidirectional"))
    )
    (net (code "89") (name "unconnected-(RELAY3-Pad4)") (class "Default")
      (node (ref "RELAY3") (pin "4") (pinfunction "4_4") (pintype "bidirectional"))
    )
    (net (code "90") (name "unconnected-(RELAY4-Pad2)") (class "Default")
      (node (ref "RELAY4") (pin "2") (pinfunction "2_2") (pintype "bidirectional"))
    )
    (net (code "91") (name "unconnected-(RELAY4-Pad3)") (class "Default")
      (node (ref "RELAY4") (pin "3") (pinfunction "3_3") (pintype "bidirectional"))
    )
    (net (code "92") (name "unconnected-(RELAY4-Pad4)") (class "Default")
      (node (ref "RELAY4") (pin "4") (pinfunction "4_4") (pintype "bidirectional"))
    )
    (net (code "93") (name "unconnected-(RELAY5-Pad2)") (class "Default")
      (node (ref "RELAY5") (pin "2") (pinfunction "2_2") (pintype "bidirectional"))
    )
    (net (code "94") (name "unconnected-(RELAY5-Pad3)") (class "Default")
      (node (ref "RELAY5") (pin "3") (pinfunction "3_3") (pintype "bidirectional"))
    )
    (net (code "95") (name "unconnected-(RELAY5-Pad4)") (class "Default")
      (node (ref "RELAY5") (pin "4") (pinfunction "4_4") (pintype "bidirectional"))
    )
    (net (code "96") (name "unconnected-(RELAY6-Pad2)") (class "Default")
      (node (ref "RELAY6") (pin "2") (pinfunction "2_2") (pintype "bidirectional"))
    )
    (net (code "97") (name "unconnected-(RELAY6-Pad3)") (class "Default")
      (node (ref "RELAY6") (pin "3") (pinfunction "3_3") (pintype "bidirectional"))
    )
    (net (code "98") (name "unconnected-(RELAY6-Pad4)") (class "Default")
      (node (ref "RELAY6") (pin "4") (pinfunction "4_4") (pintype "bidirectional"))
    )
    (net (code "99") (name "unconnected-(RELAY7-Pad2)") (class "Default")
      (node (ref "RELAY7") (pin "2") (pinfunction "2_2") (pintype "bidirectional"))
    )
    (net (code "100") (name "unconnected-(RELAY7-Pad3)") (class "Default")
      (node (ref "RELAY7") (pin "3") (pinfunction "3_3") (pintype "bidirectional"))
    )
    (net (code "101") (name "unconnected-(RELAY7-Pad4)") (class "Default")
      (node (ref "RELAY7") (pin "4") (pinfunction "4_4") (pintype "bidirectional"))
    )
    (net (code "102") (name "unconnected-(RELAY8-Pad2)") (class "Default")
      (node (ref "RELAY8") (pin "2") (pinfunction "2_2") (pintype "bidirectional"))
    )
    (net (code "103") (name "unconnected-(RELAY8-Pad3)") (class "Default")
      (node (ref "RELAY8") (pin "3") (pinfunction "3_3") (pintype "bidirectional"))
    )
    (net (code "104") (name "unconnected-(RELAY8-Pad4)") (class "Default")
      (node (ref "RELAY8") (pin "4") (pinfunction "4_4") (pintype "bidirectional"))
    )
    (net (code "105") (name "unconnected-(RELAY10-Pad2)") (class "Default")
      (node (ref "RELAY10") (pin "2") (pinfunction "2_2") (pintype "bidirectional"))
    )
    (net (code "106") (name "unconnected-(RELAY10-Pad3)") (class "Default")
      (node (ref "RELAY10") (pin "3") (pinfunction "3_3") (pintype "bidirectional"))
    )
    (net (code "107") (name "unconnected-(RELAY10-Pad4)") (class "Default")
      (node (ref "RELAY10") (pin "4") (pinfunction "4_4") (pintype "bidirectional"))
    )
    (net (code "108") (name "unconnected-(RELAY11-Pad2)") (class "Default")
      (node (ref "RELAY11") (pin "2") (pinfunction "2_2") (pintype "bidirectional"))
    )
    (net (code "109") (name "unconnected-(RELAY11-Pad3)") (class "Default")
      (node (ref "RELAY11") (pin "3") (pinfunction "3_3") (pintype "bidirectional"))
    )
    (net (code "110") (name "unconnected-(RELAY11-Pad4)") (class "Default")
      (node (ref "RELAY11") (pin "4") (pinfunction "4_4") (pintype "bidirectional"))
    )
    (net (code "111") (name "unconnected-(RELAY12-Pad2)") (class "Default")
      (node (ref "RELAY12") (pin "2") (pinfunction "2_2") (pintype "bidirectional"))
    )
    (net (code "112") (name "unconnected-(RELAY12-Pad3)") (class "Default")
      (node (ref "RELAY12") (pin "3") (pinfunction "3_3") (pintype "bidirectional"))
    )
    (net (code "113") (name "unconnected-(RELAY12-Pad4)") (class "Default")
      (node (ref "RELAY12") (pin "4") (pinfunction "4_4") (pintype "bidirectional"))
    )
    (net (code "114") (name "unconnected-(RELAY13-Pad2)") (class "Default")
      (node (ref "RELAY13") (pin "2") (pinfunction "2_2") (pintype "bidirectional"))
    )
    (net (code "115") (name "unconnected-(RELAY13-Pad3)") (class "Default")
      (node (ref "RELAY13") (pin "3") (pinfunction "3_3") (pintype "bidirectional"))
    )
    (net (code "116") (name "unconnected-(RELAY13-Pad4)") (class "Default")
      (node (ref "RELAY13") (pin "4") (pinfunction "4_4") (pintype "bidirectional"))
    )
    (net (code "117") (name "unconnected-(RELAY14-Pad2)") (class "Default")
      (node (ref "RELAY14") (pin "2") (pinfunction "2_2") (pintype "bidirectional"))
    )
    (net (code "118") (name "unconnected-(RELAY14-Pad3)") (class "Default")
      (node (ref "RELAY14") (pin "3") (pinfunction "3_3") (pintype "bidirectional"))
    )
    (net (code "119") (name "unconnected-(RELAY14-Pad4)") (class "Default")
      (node (ref "RELAY14") (pin "4") (pinfunction "4_4") (pintype "bidirectional"))
    )
    (net (code "120") (name "unconnected-(RELAY15-Pad2)") (class "Default")
      (node (ref "RELAY15") (pin "2") (pinfunction "2_2") (pintype "bidirectional"))
    )
    (net (code "121") (name "unconnected-(RELAY15-Pad3)") (class "Default")
      (node (ref "RELAY15") (pin "3") (pinfunction "3_3") (pintype "bidirectional"))
    )
    (net (code "122") (name "unconnected-(RELAY15-Pad4)") (class "Default")
      (node (ref "RELAY15") (pin "4") (pinfunction "4_4") (pintype "bidirectional"))
    )
    (net (code "123") (name "unconnected-(RELAY16-Pad2)") (class "Default")
      (node (ref "RELAY16") (pin "2") (pinfunction "2_2") (pintype "bidirectional"))
    )
    (net (code "124") (name "unconnected-(RELAY16-Pad3)") (class "Default")
      (node (ref "RELAY16") (pin "3") (pinfunction "3_3") (pintype "bidirectional"))
    )
    (net (code "125") (name "unconnected-(RELAY16-Pad4)") (class "Default")
      (node (ref "RELAY16") (pin "4") (pinfunction "4_4") (pintype "bidirectional"))
    )
    (net (code "126") (name "unconnected-(RELAY17-Pad2)") (class "Default")
      (node (ref "RELAY17") (pin "2") (pinfunction "2_2") (pintype "bidirectional"))
    )
    (net (code "127") (name "unconnected-(RELAY17-Pad3)") (class "Default")
      (node (ref "RELAY17") (pin "3") (pinfunction "3_3") (pintype "bidirectional"))
    )
    (net (code "128") (name "unconnected-(RELAY17-Pad4)") (class "Default")
      (node (ref "RELAY17") (pin "4") (pinfunction "4_4") (pintype "bidirectional"))
    )
    (net (code "129") (name "unconnected-(RELAY18-Pad2)") (class "Default")
      (node (ref "RELAY18") (pin "2") (pinfunction "2_2") (pintype "bidirectional"))
    )
    (net (code "130") (name "unconnected-(RELAY18-Pad3)") (class "Default")
      (node (ref "RELAY18") (pin "3") (pinfunction "3_3") (pintype "bidirectional"))
    )
    (net (code "131") (name "unconnected-(RELAY18-Pad4)") (class "Default")
      (node (ref "RELAY18") (pin "4") (pinfunction "4_4") (pintype "bidirectional"))
    )
    (net (code "132") (name "unconnected-(RELAY19-Pad2)") (class "Default")
      (node (ref "RELAY19") (pin "2") (pinfunction "2_2") (pintype "bidirectional"))
    )
    (net (code "133") (name "unconnected-(RELAY19-Pad3)") (class "Default")
      (node (ref "RELAY19") (pin "3") (pinfunction "3_3") (pintype "bidirectional"))
    )
    (net (code "134") (name "unconnected-(RELAY19-Pad4)") (class "Default")
      (node (ref "RELAY19") (pin "4") (pinfunction "4_4") (pintype "bidirectional"))
    )
    (net (code "135") (name "unconnected-(RELAY20-Pad2)") (class "Default")
      (node (ref "RELAY20") (pin "2") (pinfunction "2_2") (pintype "bidirectional"))
    )
    (net (code "136") (name "unconnected-(RELAY20-Pad3)") (class "Default")
      (node (ref "RELAY20") (pin "3") (pinfunction "3_3") (pintype "bidirectional"))
    )
    (net (code "137") (name "unconnected-(RELAY20-Pad4)") (class "Default")
      (node (ref "RELAY20") (pin "4") (pinfunction "4_4") (pintype "bidirectional"))
    )
    (net (code "138") (name "unconnected-(RELAY21-Pad2)") (class "Default")
      (node (ref "RELAY21") (pin "2") (pinfunction "2_2") (pintype "bidirectional"))
    )
    (net (code "139") (name "unconnected-(RELAY21-Pad3)") (class "Default")
      (node (ref "RELAY21") (pin "3") (pinfunction "3_3") (pintype "bidirectional"))
    )
    (net (code "140") (name "unconnected-(RELAY21-Pad4)") (class "Default")
      (node (ref "RELAY21") (pin "4") (pinfunction "4_4") (pintype "bidirectional"))
    )
    (net (code "141") (name "unconnected-(RELAY22-Pad2)") (class "Default")
      (node (ref "RELAY22") (pin "2") (pinfunction "2_2") (pintype "bidirectional"))
    )
    (net (code "142") (name "unconnected-(RELAY22-Pad3)") (class "Default")
      (node (ref "RELAY22") (pin "3") (pinfunction "3_3") (pintype "bidirectional"))
    )
    (net (code "143") (name "unconnected-(RELAY22-Pad4)") (class "Default")
      (node (ref "RELAY22") (pin "4") (pinfunction "4_4") (pintype "bidirectional"))
    )
    (net (code "144") (name "unconnected-(RELAY23-Pad2)") (class "Default")
      (node (ref "RELAY23") (pin "2") (pinfunction "2_2") (pintype "bidirectional"))
    )
    (net (code "145") (name "unconnected-(RELAY23-Pad3)") (class "Default")
      (node (ref "RELAY23") (pin "3") (pinfunction "3_3") (pintype "bidirectional"))
    )
    (net (code "146") (name "unconnected-(RELAY23-Pad4)") (class "Default")
      (node (ref "RELAY23") (pin "4") (pinfunction "4_4") (pintype "bidirectional"))
    )
    (net (code "147") (name "unconnected-(RELAY24-Pad2)") (class "Default")
      (node (ref "RELAY24") (pin "2") (pinfunction "2_2") (pintype "bidirectional"))
    )
    (net (code "148") (name "unconnected-(RELAY24-Pad3)") (class "Default")
      (node (ref "RELAY24") (pin "3") (pinfunction "3_3") (pintype "bidirectional"))
    )
    (net (code "149") (name "unconnected-(RELAY24-Pad4)") (class "Default")
      (node (ref "RELAY24") (pin "4") (pinfunction "4_4") (pintype "bidirectional"))
    )
    (net (code "150") (name "unconnected-(RELAY25-Pad2)") (class "Default")
      (node (ref "RELAY25") (pin "2") (pinfunction "2_2") (pintype "bidirectional"))
    )
    (net (code "151") (name "unconnected-(RELAY25-Pad3)") (class "Default")
      (node (ref "RELAY25") (pin "3") (pinfunction "3_3") (pintype "bidirectional"))
    )
    (net (code "152") (name "unconnected-(RELAY25-Pad4)") (class "Default")
      (node (ref "RELAY25") (pin "4") (pinfunction "4_4") (pintype "bidirectional"))
    )
    (net (code "153") (name "unconnected-(RELAY26-Pad2)") (class "Default")
      (node (ref "RELAY26") (pin "2") (pinfunction "2_2") (pintype "bidirectional"))
    )
    (net (code "154") (name "unconnected-(RELAY26-Pad3)") (class "Default")
      (node (ref "RELAY26") (pin "3") (pinfunction "3_3") (pintype "bidirectional"))
    )
    (net (code "155") (name "unconnected-(RELAY26-Pad4)") (class "Default")
      (node (ref "RELAY26") (pin "4") (pinfunction "4_4") (pintype "bidirectional"))
    )
    (net (code "156") (name "unconnected-(RELAY27-Pad2)") (class "Default")
      (node (ref "RELAY27") (pin "2") (pinfunction "2_2") (pintype "bidirectional"))
    )
    (net (code "157") (name "unconnected-(RELAY27-Pad3)") (class "Default")
      (node (ref "RELAY27") (pin "3") (pinfunction "3_3") (pintype "bidirectional"))
    )
    (net (code "158") (name "unconnected-(RELAY27-Pad4)") (class "Default")
      (node (ref "RELAY27") (pin "4") (pinfunction "4_4") (pintype "bidirectional"))
    )
    (net (code "159") (name "unconnected-(RELAY28-Pad2)") (class "Default")
      (node (ref "RELAY28") (pin "2") (pinfunction "2_2") (pintype "bidirectional"))
    )
    (net (code "160") (name "unconnected-(RELAY28-Pad3)") (class "Default")
      (node (ref "RELAY28") (pin "3") (pinfunction "3_3") (pintype "bidirectional"))
    )
    (net (code "161") (name "unconnected-(RELAY28-Pad4)") (class "Default")
      (node (ref "RELAY28") (pin "4") (pinfunction "4_4") (pintype "bidirectional"))
    )
    (net (code "162") (name "unconnected-(RELAY29-Pad2)") (class "Default")
      (node (ref "RELAY29") (pin "2") (pinfunction "2_2") (pintype "bidirectional"))
    )
    (net (code "163") (name "unconnected-(RELAY29-Pad3)") (class "Default")
      (node (ref "RELAY29") (pin "3") (pinfunction "3_3") (pintype "bidirectional"))
    )
    (net (code "164") (name "unconnected-(RELAY29-Pad4)") (class "Default")
      (node (ref "RELAY29") (pin "4") (pinfunction "4_4") (pintype "bidirectional"))
    )
    (net (code "165") (name "unconnected-(RELAY30-Pad2)") (class "Default")
      (node (ref "RELAY30") (pin "2") (pinfunction "2_2") (pintype "bidirectional"))
    )
    (net (code "166") (name "unconnected-(RELAY30-Pad3)") (class "Default")
      (node (ref "RELAY30") (pin "3") (pinfunction "3_3") (pintype "bidirectional"))
    )
    (net (code "167") (name "unconnected-(RELAY30-Pad4)") (class "Default")
      (node (ref "RELAY30") (pin "4") (pinfunction "4_4") (pintype "bidirectional"))
    )
    (net (code "168") (name "unconnected-(RELAY31-Pad2)") (class "Default")
      (node (ref "RELAY31") (pin "2") (pinfunction "2_2") (pintype "bidirectional"))
    )
    (net (code "169") (name "unconnected-(RELAY31-Pad3)") (class "Default")
      (node (ref "RELAY31") (pin "3") (pinfunction "3_3") (pintype "bidirectional"))
    )
    (net (code "170") (name "unconnected-(RELAY31-Pad4)") (class "Default")
      (node (ref "RELAY31") (pin "4") (pinfunction "4_4") (pintype "bidirectional"))
    )
    (net (code "171") (name "unconnected-(RELAY32-Pad2)") (class "Default")
      (node (ref "RELAY32") (pin "2") (pinfunction "2_2") (pintype "bidirectional"))
    )
    (net (code "172") (name "unconnected-(RELAY32-Pad3)") (class "Default")
      (node (ref "RELAY32") (pin "3") (pinfunction "3_3") (pintype "bidirectional"))
    )
    (net (code "173") (name "unconnected-(RELAY32-Pad4)") (class "Default")
      (node (ref "RELAY32") (pin "4") (pinfunction "4_4") (pintype "bidirectional"))
    )
    (net (code "174") (name "unconnected-(RELAY33-Pad2)") (class "Default")
      (node (ref "RELAY33") (pin "2") (pinfunction "2_2") (pintype "bidirectional"))
    )
    (net (code "175") (name "unconnected-(RELAY33-Pad3)") (class "Default")
      (node (ref "RELAY33") (pin "3") (pinfunction "3_3") (pintype "bidirectional"))
    )
    (net (code "176") (name "unconnected-(RELAY33-Pad4)") (class "Default")
      (node (ref "RELAY33") (pin "4") (pinfunction "4_4") (pintype "bidirectional"))
    )
  )
)
